# CPU.net
KiCad netlist of a schematic drawn in Altium Designer
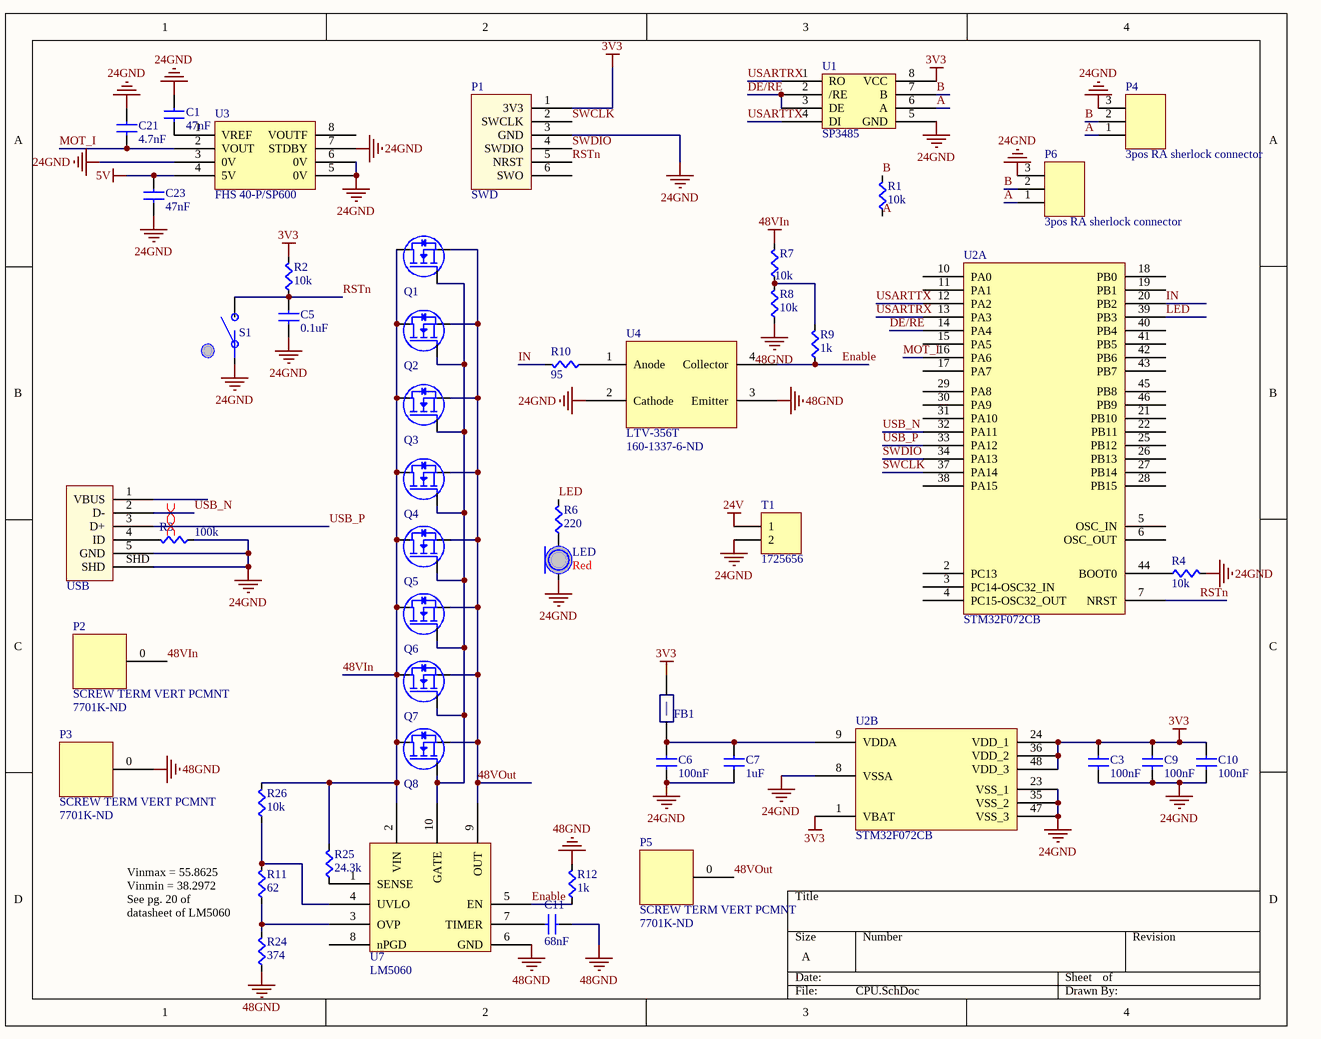
[diagram p0: CPU.SchDoc]

(export (version "E")
  (design (tool "Eeschema 10.0.6"))
  (components
    (comp (ref "C1")
      (value "47nF")
      (footprint "CAPC0603")
      (fields (field (name "Comment") "Cap"))
      (libsource (lib "SubjuGator8") (part "Cap"))
    )
    (comp (ref "C3")
      (value "100nF")
      (footprint "CAPC0603")
      (fields (field (name "Comment") "Cap"))
      (libsource (lib "SubjuGator8") (part "Cap"))
    )
    (comp (ref "C5")
      (value "0.1uF")
      (footprint "CAPC0603")
      (fields (field (name "Comment") "Cap"))
      (libsource (lib "SubjuGator8") (part "Cap"))
    )
    (comp (ref "C6")
      (value "100nF")
      (footprint "CAPC0603")
      (fields (field (name "Comment") "Cap"))
      (libsource (lib "SubjuGator8") (part "Cap"))
    )
    (comp (ref "C7")
      (value "1uF")
      (footprint "CAPC0603")
      (fields (field (name "Comment") "Cap"))
      (libsource (lib "SubjuGator8") (part "Cap"))
    )
    (comp (ref "C9")
      (value "100nF")
      (footprint "CAPC0603")
      (fields (field (name "Comment") "Cap"))
      (libsource (lib "SubjuGator8") (part "Cap"))
    )
    (comp (ref "C10")
      (value "100nF")
      (footprint "CAPC0603")
      (fields (field (name "Comment") "Cap"))
      (libsource (lib "SubjuGator8") (part "Cap"))
    )
    (comp (ref "C11")
      (value "68nF")
      (footprint "CAPC0603")
      (fields (field (name "Comment") "Cap"))
      (libsource (lib "SubjuGator8") (part "Cap"))
    )
    (comp (ref "C21")
      (value "4.7nF")
      (footprint "CAPC0603")
      (fields (field (name "Comment") "Cap"))
      (libsource (lib "SubjuGator8") (part "Cap"))
    )
    (comp (ref "C23")
      (value "47nF")
      (footprint "CAPC0603")
      (fields (field (name "Comment") "Cap"))
      (libsource (lib "SubjuGator8") (part "Cap"))
    )
    (comp (ref "FB1")
      (value "FBead")
      (footprint "RES0603")
      (description "Ferrite Bead")
      (libsource (lib "SubjuGator8") (part "FBead"))
    )
    (comp (ref "LED")
      (value "LED")
      (footprint "LED0603")
      (fields (field (name "COLOR") "Red"))
      (libsource (lib "SubjuGator8") (part "LED"))
    )
    (comp (ref "P1")
      (value "SWD")
      (footprint "SWD_STM32")
      (description "SWD connector matching the pinout on STM Discovery Boards")
      (libsource (lib "SubjuGator8") (part "SWD_STM32"))
    )
    (comp (ref "P2")
      (value "SCREW TERM VERT PCMNT")
      (footprint "SCREW TERM SINGLE VERT")
      (description "Keystone Electronics 7701")
      (fields (field (name "SUPPLIER PART NUMBER 1") "7701K-ND"))
      (libsource (lib "SubjuGator8") (part "SCREW TERM VERT PCMNT"))
    )
    (comp (ref "P3")
      (value "SCREW TERM VERT PCMNT")
      (footprint "SCREW TERM SINGLE VERT")
      (description "Keystone Electronics 7701")
      (fields (field (name "SUPPLIER PART NUMBER 1") "7701K-ND"))
      (libsource (lib "SubjuGator8") (part "SCREW TERM VERT PCMNT"))
    )
    (comp (ref "P4")
      (value "3pos RA sherlock connector")
      (footprint "MOLEX-HDR-1X3-SHERLOCK-RA")
      (description "Header, Molex, 2mm Pitch Sherlock Header, Single Row, Right Angle 3 Circuits, Length 3.3mm")
      (fields
        (field (name "MANUFACTURER PART NUMBER") "35363-0360")
        (field (name "MANUFACTURER") "Molex Connector Corporation")
      )
      (libsource (lib "SubjuGator8") (part "MOLEX-HDR-1x3-SHERLOCK_RA"))
    )
    (comp (ref "P5")
      (value "SCREW TERM VERT PCMNT")
      (footprint "SCREW TERM SINGLE VERT")
      (description "Keystone Electronics 7701")
      (fields (field (name "SUPPLIER PART NUMBER 1") "7701K-ND"))
      (libsource (lib "SubjuGator8") (part "SCREW TERM VERT PCMNT"))
    )
    (comp (ref "P6")
      (value "3pos RA sherlock connector")
      (footprint "MOLEX-HDR-1X3-SHERLOCK-RA")
      (description "Header, Molex, 2mm Pitch Sherlock Header, Single Row, Right Angle 3 Circuits, Length 3.3mm")
      (fields
        (field (name "MANUFACTURER PART NUMBER") "35363-0360")
        (field (name "MANUFACTURER") "Molex Connector Corporation")
      )
      (libsource (lib "SubjuGator8") (part "MOLEX-HDR-1x3-SHERLOCK_RA"))
    )
    (comp (ref "Q1")
      (value "CSD19502Q5B")
      (footprint "CSD19502Q5B")
      (description "NEXFET Power MOSFET")
      (libsource (lib "SubjuGator8") (part "CSD19502Q5B"))
    )
    (comp (ref "Q2")
      (value "CSD19502Q5B")
      (footprint "CSD19502Q5B")
      (description "NEXFET Power MOSFET")
      (libsource (lib "SubjuGator8") (part "CSD19502Q5B"))
    )
    (comp (ref "Q3")
      (value "CSD19502Q5B")
      (footprint "CSD19502Q5B")
      (description "NEXFET Power MOSFET")
      (libsource (lib "SubjuGator8") (part "CSD19502Q5B"))
    )
    (comp (ref "Q4")
      (value "CSD19502Q5B")
      (footprint "CSD19502Q5B")
      (description "NEXFET Power MOSFET")
      (libsource (lib "SubjuGator8") (part "CSD19502Q5B"))
    )
    (comp (ref "Q5")
      (value "CSD19502Q5B")
      (footprint "CSD19502Q5B")
      (description "NEXFET Power MOSFET")
      (libsource (lib "SubjuGator8") (part "CSD19502Q5B"))
    )
    (comp (ref "Q6")
      (value "CSD19502Q5B")
      (footprint "CSD19502Q5B")
      (description "NEXFET Power MOSFET")
      (libsource (lib "SubjuGator8") (part "CSD19502Q5B"))
    )
    (comp (ref "Q7")
      (value "CSD19502Q5B")
      (footprint "CSD19502Q5B")
      (description "NEXFET Power MOSFET")
      (libsource (lib "SubjuGator8") (part "CSD19502Q5B"))
    )
    (comp (ref "Q8")
      (value "CSD19502Q5B")
      (footprint "CSD19502Q5B")
      (description "NEXFET Power MOSFET")
      (libsource (lib "SubjuGator8") (part "CSD19502Q5B"))
    )
    (comp (ref "R1")
      (value "10k")
      (footprint "RES0603")
      (fields (field (name "Comment") "Res"))
      (libsource (lib "SubjuGator8") (part "Res"))
    )
    (comp (ref "R2")
      (value "10k")
      (footprint "RES0603")
      (fields (field (name "Comment") "Res"))
      (libsource (lib "SubjuGator8") (part "Res"))
    )
    (comp (ref "R3")
      (value "100k")
      (footprint "RES0603")
      (fields (field (name "Comment") "Res"))
      (libsource (lib "SubjuGator8") (part "Res"))
    )
    (comp (ref "R4")
      (value "10k")
      (footprint "RES0603")
      (fields (field (name "Comment") "Res"))
      (libsource (lib "SubjuGator8") (part "Res"))
    )
    (comp (ref "R6")
      (value "220")
      (footprint "RES0603")
      (fields (field (name "Comment") "Res"))
      (libsource (lib "SubjuGator8") (part "Res"))
    )
    (comp (ref "R7")
      (value "10k")
      (footprint "RES0603")
      (fields (field (name "Comment") "Res"))
      (libsource (lib "SubjuGator8") (part "Res"))
    )
    (comp (ref "R8")
      (value "10k")
      (footprint "RES0603")
      (fields (field (name "Comment") "Res"))
      (libsource (lib "SubjuGator8") (part "Res"))
    )
    (comp (ref "R9")
      (value "1k")
      (footprint "RES0603")
      (fields (field (name "Comment") "Res"))
      (libsource (lib "SubjuGator8") (part "Res"))
    )
    (comp (ref "R10")
      (value "95")
      (footprint "RES0603")
      (fields (field (name "Comment") "Res"))
      (libsource (lib "SubjuGator8") (part "Res"))
    )
    (comp (ref "R11")
      (value "62")
      (footprint "RES0603")
      (fields (field (name "Comment") "Res"))
      (libsource (lib "SubjuGator8") (part "Res"))
    )
    (comp (ref "R12")
      (value "1k")
      (footprint "RES0603")
      (fields (field (name "Comment") "Res"))
      (libsource (lib "SubjuGator8") (part "Res"))
    )
    (comp (ref "R24")
      (value "374")
      (footprint "RES0603")
      (fields (field (name "Comment") "Res"))
      (libsource (lib "SubjuGator8") (part "Res"))
    )
    (comp (ref "R25")
      (value "24.3k")
      (footprint "RES0603")
      (fields (field (name "Comment") "Res"))
      (libsource (lib "SubjuGator8") (part "Res"))
    )
    (comp (ref "R26")
      (value "10k")
      (footprint "RES0603")
      (fields (field (name "Comment") "Res"))
      (libsource (lib "SubjuGator8") (part "Res"))
    )
    (comp (ref "S1")
      (value "Button")
      (footprint "PTS645xxxxSMTR92")
      (description "SPST Button")
      (libsource (lib "SubjuGator8") (part "Button"))
    )
    (comp (ref "T1")
      (value "1725656")
      (footprint "1725656")
      (description "CONN TERM BLOCK 2.54MM 2POS")
      (libsource (lib "SubjuGator8") (part "1725656"))
    )
    (comp (ref "U1")
      (value "SP3485")
      (footprint "SP3485")
      (description "IC TXRX RS485 HALF DUPLEX 8NSOIC")
      (libsource (lib "SubjuGator8") (part "SP3485"))
    )
    (comp (ref "U2")
      (value "STM32F072CB")
      (footprint "STM32F072CB")
      (description "MCU 32BIT 128KB FLASH 48LQFP")
      (libsource (lib "SubjuGator8") (part "STM32F072CB"))
    )
    (comp (ref "U3")
      (value "FHS 40-P/SP600")
      (footprint "FHS 40-P/SP600")
      (libsource (lib "SubjuGator8") (part "FHS 40-P/SP600"))
    )
    (comp (ref "U4")
      (value "LTV-356T")
      (footprint "LTV-356T")
      (description "OPTOISOLATOR 3.75KV TRANS 4-SOP")
      (fields (field (name "SUPPLIER PART NUMBER 1") "160-1337-6-ND"))
      (libsource (lib "SubjuGator8") (part "LTV-356T"))
    )
    (comp (ref "U7")
      (value "LM5060")
      (footprint "LM5060")
      (description "Hotswap Controller")
      (libsource (lib "SubjuGator8") (part "LM5060"))
    )
    (comp (ref "USB")
      (value "USB Micro")
      (footprint "10118192-0001LF")
      (description "USB Mini B Metal Shield SMT")
      (libsource (lib "SubjuGator8") (part "USB Micro"))
    )
  )
  (nets
    (net (code "1") (name "/48VOut") (class "Default")
      (node (ref "P5") (pin "0") (pinfunction "1_0") (pintype "passive"))
      (node (ref "Q1") (pin "S") (pinfunction "S_S") (pintype "passive"))
      (node (ref "Q2") (pin "S") (pinfunction "S_S") (pintype "passive"))
      (node (ref "Q3") (pin "S") (pinfunction "S_S") (pintype "passive"))
      (node (ref "Q4") (pin "S") (pinfunction "S_S") (pintype "passive"))
      (node (ref "Q5") (pin "S") (pinfunction "S_S") (pintype "passive"))
      (node (ref "Q6") (pin "S") (pinfunction "S_S") (pintype "passive"))
      (node (ref "Q7") (pin "S") (pinfunction "S_S") (pintype "passive"))
      (node (ref "Q8") (pin "S") (pinfunction "S_S") (pintype "passive"))
      (node (ref "U7") (pin "9") (pinfunction "OUT_9") (pintype "passive"))
    )
    (net (code "2") (name "/A") (class "Default")
      (node (ref "P4") (pin "1") (pinfunction "1_1") (pintype "passive"))
      (node (ref "P6") (pin "1") (pinfunction "1_1") (pintype "passive"))
      (node (ref "R1") (pin "2") (pinfunction "B_2") (pintype "passive"))
      (node (ref "U1") (pin "6") (pinfunction "A_6") (pintype "passive"))
    )
    (net (code "3") (name "/B") (class "Default")
      (node (ref "P4") (pin "2") (pinfunction "2_2") (pintype "passive"))
      (node (ref "P6") (pin "2") (pinfunction "2_2") (pintype "passive"))
      (node (ref "R1") (pin "1") (pinfunction "A_1") (pintype "passive"))
      (node (ref "U1") (pin "7") (pinfunction "B_7") (pintype "passive"))
    )
    (net (code "4") (name "/DE{slash}RE") (class "Default")
      (node (ref "U1") (pin "2") (pinfunction "/RE_2") (pintype "passive"))
      (node (ref "U1") (pin "3") (pinfunction "DE_3") (pintype "passive"))
      (node (ref "U2") (pin "14") (pinfunction "PA4_14") (pintype "passive"))
    )
    (net (code "5") (name "/Enable") (class "Default")
      (node (ref "R12") (pin "2") (pinfunction "B_2") (pintype "passive"))
      (node (ref "R9") (pin "2") (pinfunction "B_2") (pintype "passive"))
      (node (ref "U4") (pin "4") (pinfunction "Collector_4") (pintype "passive"))
      (node (ref "U7") (pin "5") (pinfunction "EN_5") (pintype "passive"))
    )
    (net (code "6") (name "/IN") (class "Default")
      (node (ref "R10") (pin "1") (pinfunction "A_1") (pintype "passive"))
      (node (ref "U2") (pin "20") (pinfunction "PB2_20") (pintype "passive"))
    )
    (net (code "7") (name "/LED") (class "Default")
      (node (ref "R6") (pin "1") (pinfunction "A_1") (pintype "passive"))
      (node (ref "U2") (pin "39") (pinfunction "PB3_39") (pintype "passive"))
    )
    (net (code "8") (name "/MOT_I") (class "Default")
      (node (ref "C21") (pin "1") (pinfunction "A_1") (pintype "passive"))
      (node (ref "U2") (pin "16") (pinfunction "PA6_16") (pintype "passive"))
      (node (ref "U3") (pin "2") (pinfunction "VOUT_2") (pintype "passive"))
    )
    (net (code "9") (name "/RSTn") (class "Default")
      (node (ref "C5") (pin "1") (pinfunction "A_1") (pintype "passive"))
      (node (ref "P1") (pin "5") (pinfunction "NRST_5") (pintype "passive"))
      (node (ref "R2") (pin "2") (pinfunction "B_2") (pintype "passive"))
      (node (ref "S1") (pin "B") (pinfunction "B_B") (pintype "passive"))
      (node (ref "U2") (pin "7") (pinfunction "NRST_7") (pintype "passive"))
    )
    (net (code "10") (name "/SWCLK") (class "Default")
      (node (ref "P1") (pin "2") (pinfunction "SWCLK_2") (pintype "passive"))
      (node (ref "U2") (pin "37") (pinfunction "PA14_37") (pintype "passive"))
    )
    (net (code "11") (name "/SWDIO") (class "Default")
      (node (ref "P1") (pin "4") (pinfunction "SWDIO_4") (pintype "passive"))
      (node (ref "U2") (pin "34") (pinfunction "PA13_34") (pintype "passive"))
    )
    (net (code "12") (name "/USARTRX") (class "Default")
      (node (ref "U1") (pin "1") (pinfunction "RO_1") (pintype "passive"))
      (node (ref "U2") (pin "13") (pinfunction "PA3_13") (pintype "passive"))
    )
    (net (code "13") (name "/USARTTX") (class "Default")
      (node (ref "U1") (pin "4") (pinfunction "DI_4") (pintype "passive"))
      (node (ref "U2") (pin "12") (pinfunction "PA2_12") (pintype "passive"))
    )
    (net (code "14") (name "/USB_N") (class "Default")
      (node (ref "U2") (pin "32") (pinfunction "PA11_32") (pintype "passive"))
      (node (ref "USB") (pin "2") (pinfunction "D-_2") (pintype "passive"))
    )
    (net (code "15") (name "/USB_P") (class "Default")
      (node (ref "U2") (pin "33") (pinfunction "PA12_33") (pintype "passive"))
      (node (ref "USB") (pin "3") (pinfunction "D+_3") (pintype "passive"))
    )
    (net (code "16") (name "3V3") (class "Default")
      (node (ref "C10") (pin "1") (pinfunction "A_1") (pintype "passive"))
      (node (ref "C3") (pin "1") (pinfunction "A_1") (pintype "passive"))
      (node (ref "C9") (pin "1") (pinfunction "A_1") (pintype "passive"))
      (node (ref "FB1") (pin "2") (pinfunction "B_2") (pintype "passive"))
      (node (ref "P1") (pin "1") (pinfunction "3V3_1") (pintype "passive"))
      (node (ref "R2") (pin "1") (pinfunction "A_1") (pintype "passive"))
      (node (ref "U1") (pin "8") (pinfunction "VCC_8") (pintype "passive"))
      (node (ref "U2") (pin "1") (pinfunction "VBAT_1") (pintype "passive"))
      (node (ref "U2") (pin "24") (pinfunction "VDD_1_24") (pintype "passive"))
      (node (ref "U2") (pin "36") (pinfunction "VDD_2_36") (pintype "passive"))
      (node (ref "U2") (pin "48") (pinfunction "VDD_3_48") (pintype "passive"))
    )
    (net (code "17") (name "5V") (class "Default")
      (node (ref "C23") (pin "1") (pinfunction "A_1") (pintype "passive"))
      (node (ref "U3") (pin "4") (pinfunction "5V_4") (pintype "passive"))
    )
    (net (code "18") (name "24GND") (class "Default")
      (node (ref "C1") (pin "1") (pinfunction "A_1") (pintype "passive"))
      (node (ref "C10") (pin "2") (pinfunction "B_2") (pintype "passive"))
      (node (ref "C21") (pin "2") (pinfunction "B_2") (pintype "passive"))
      (node (ref "C23") (pin "2") (pinfunction "B_2") (pintype "passive"))
      (node (ref "C3") (pin "2") (pinfunction "B_2") (pintype "passive"))
      (node (ref "C5") (pin "2") (pinfunction "B_2") (pintype "passive"))
      (node (ref "C6") (pin "2") (pinfunction "B_2") (pintype "passive"))
      (node (ref "C7") (pin "2") (pinfunction "B_2") (pintype "passive"))
      (node (ref "C9") (pin "2") (pinfunction "B_2") (pintype "passive"))
      (node (ref "LED") (pin "C") (pinfunction "C_C") (pintype "passive"))
      (node (ref "P1") (pin "3") (pinfunction "GND_3") (pintype "passive"))
      (node (ref "P4") (pin "3") (pinfunction "3_3") (pintype "passive"))
      (node (ref "P6") (pin "3") (pinfunction "3_3") (pintype "passive"))
      (node (ref "R3") (pin "2") (pinfunction "B_2") (pintype "passive"))
      (node (ref "R4") (pin "1") (pinfunction "A_1") (pintype "passive"))
      (node (ref "S1") (pin "A") (pinfunction "A_A") (pintype "passive"))
      (node (ref "T1") (pin "2") (pinfunction "2_2") (pintype "passive"))
      (node (ref "U1") (pin "5") (pinfunction "GND_5") (pintype "passive"))
      (node (ref "U2") (pin "23") (pinfunction "VSS_1_23") (pintype "passive"))
      (node (ref "U2") (pin "35") (pinfunction "VSS_2_35") (pintype "passive"))
      (node (ref "U2") (pin "47") (pinfunction "VSS_3_47") (pintype "passive"))
      (node (ref "U2") (pin "8") (pinfunction "VSSA_8") (pintype "passive"))
      (node (ref "U3") (pin "3") (pinfunction "0V_3") (pintype "passive"))
      (node (ref "U3") (pin "5") (pinfunction "0V_5") (pintype "passive"))
      (node (ref "U3") (pin "6") (pinfunction "0V_6") (pintype "passive"))
      (node (ref "U3") (pin "7") (pinfunction "STDBY_7") (pintype "passive"))
      (node (ref "U4") (pin "2") (pinfunction "Cathode_2") (pintype "passive"))
      (node (ref "USB") (pin "5") (pinfunction "GND_5") (pintype "passive"))
      (node (ref "USB") (pin "SHD") (pinfunction "SHD_SHD") (pintype "passive"))
    )
    (net (code "19") (name "24V") (class "Default")
      (node (ref "T1") (pin "1") (pinfunction "1_1") (pintype "passive"))
    )
    (net (code "20") (name "48GND") (class "Default")
      (node (ref "C11") (pin "2") (pinfunction "B_2") (pintype "passive"))
      (node (ref "P3") (pin "0") (pinfunction "1_0") (pintype "passive"))
      (node (ref "R12") (pin "1") (pinfunction "A_1") (pintype "passive"))
      (node (ref "R24") (pin "2") (pinfunction "B_2") (pintype "passive"))
      (node (ref "R8") (pin "2") (pinfunction "B_2") (pintype "passive"))
      (node (ref "U4") (pin "3") (pinfunction "Emitter_3") (pintype "passive"))
      (node (ref "U7") (pin "6") (pinfunction "GND_6") (pintype "passive"))
    )
    (net (code "21") (name "48VIn") (class "Default")
      (node (ref "P2") (pin "0") (pinfunction "1_0") (pintype "passive"))
      (node (ref "Q1") (pin "D") (pinfunction "D_D") (pintype "passive"))
      (node (ref "Q2") (pin "D") (pinfunction "D_D") (pintype "passive"))
      (node (ref "Q3") (pin "D") (pinfunction "D_D") (pintype "passive"))
      (node (ref "Q4") (pin "D") (pinfunction "D_D") (pintype "passive"))
      (node (ref "Q5") (pin "D") (pinfunction "D_D") (pintype "passive"))
      (node (ref "Q6") (pin "D") (pinfunction "D_D") (pintype "passive"))
      (node (ref "Q7") (pin "D") (pinfunction "D_D") (pintype "passive"))
      (node (ref "Q8") (pin "D") (pinfunction "D_D") (pintype "passive"))
      (node (ref "R25") (pin "1") (pinfunction "A_1") (pintype "passive"))
      (node (ref "R26") (pin "1") (pinfunction "A_1") (pintype "passive"))
      (node (ref "R7") (pin "1") (pinfunction "A_1") (pintype "passive"))
      (node (ref "U7") (pin "2") (pinfunction "VIN_2") (pintype "passive"))
    )
    (net (code "22") (name "Net-(C1-B)") (class "Default")
      (node (ref "C1") (pin "2") (pinfunction "B_2") (pintype "passive"))
      (node (ref "U3") (pin "1") (pinfunction "VREF_1") (pintype "passive"))
    )
    (net (code "23") (name "Net-(C6-A)") (class "Default")
      (node (ref "C6") (pin "1") (pinfunction "A_1") (pintype "passive"))
      (node (ref "C7") (pin "1") (pinfunction "A_1") (pintype "passive"))
      (node (ref "FB1") (pin "1") (pinfunction "A_1") (pintype "passive"))
      (node (ref "U2") (pin "9") (pinfunction "VDDA_9") (pintype "passive"))
    )
    (net (code "24") (name "Net-(C11-A)") (class "Default")
      (node (ref "C11") (pin "1") (pinfunction "A_1") (pintype "passive"))
      (node (ref "U7") (pin "7") (pinfunction "TIMER_7") (pintype "passive"))
    )
    (net (code "25") (name "Net-(R3-A)") (class "Default")
      (node (ref "R3") (pin "1") (pinfunction "A_1") (pintype "passive"))
      (node (ref "USB") (pin "4") (pinfunction "ID_4") (pintype "passive"))
    )
    (net (code "26") (name "Net-(R4-B)") (class "Default")
      (node (ref "R4") (pin "2") (pinfunction "B_2") (pintype "passive"))
      (node (ref "U2") (pin "44") (pinfunction "BOOT0_44") (pintype "passive"))
    )
    (net (code "27") (name "Net-(R6-B)") (class "Default")
      (node (ref "LED") (pin "A") (pinfunction "A_A") (pintype "passive"))
      (node (ref "R6") (pin "2") (pinfunction "B_2") (pintype "passive"))
    )
    (net (code "28") (name "Net-(R7-B)") (class "Default")
      (node (ref "R7") (pin "2") (pinfunction "B_2") (pintype "passive"))
      (node (ref "R8") (pin "1") (pinfunction "A_1") (pintype "passive"))
      (node (ref "R9") (pin "1") (pinfunction "A_1") (pintype "passive"))
    )
    (net (code "29") (name "Net-(R10-B)") (class "Default")
      (node (ref "R10") (pin "2") (pinfunction "B_2") (pintype "passive"))
      (node (ref "U4") (pin "1") (pinfunction "Anode_1") (pintype "passive"))
    )
    (net (code "30") (name "Net-(R11-A)") (class "Default")
      (node (ref "R11") (pin "1") (pinfunction "A_1") (pintype "passive"))
      (node (ref "R26") (pin "2") (pinfunction "B_2") (pintype "passive"))
      (node (ref "U7") (pin "4") (pinfunction "UVLO_4") (pintype "passive"))
    )
    (net (code "31") (name "Net-(R11-B)") (class "Default")
      (node (ref "R11") (pin "2") (pinfunction "B_2") (pintype "passive"))
      (node (ref "R24") (pin "1") (pinfunction "A_1") (pintype "passive"))
      (node (ref "U7") (pin "3") (pinfunction "OVP_3") (pintype "passive"))
    )
    (net (code "32") (name "Net-(R25-B)") (class "Default")
      (node (ref "R25") (pin "2") (pinfunction "B_2") (pintype "passive"))
      (node (ref "U7") (pin "1") (pinfunction "SENSE_1") (pintype "passive"))
    )
    (net (code "33") (name "Net-(U7-GATE)") (class "Default")
      (node (ref "Q1") (pin "G") (pinfunction "G_G") (pintype "passive"))
      (node (ref "Q2") (pin "G") (pinfunction "G_G") (pintype "passive"))
      (node (ref "Q3") (pin "G") (pinfunction "G_G") (pintype "passive"))
      (node (ref "Q4") (pin "G") (pinfunction "G_G") (pintype "passive"))
      (node (ref "Q5") (pin "G") (pinfunction "G_G") (pintype "passive"))
      (node (ref "Q6") (pin "G") (pinfunction "G_G") (pintype "passive"))
      (node (ref "Q7") (pin "G") (pinfunction "G_G") (pintype "passive"))
      (node (ref "Q8") (pin "G") (pinfunction "G_G") (pintype "passive"))
      (node (ref "U7") (pin "10") (pinfunction "GATE_10") (pintype "passive"))
    )
    (net (code "34") (name "unconnected-(P1-SWO-Pad6)") (class "Default")
      (node (ref "P1") (pin "6") (pinfunction "SWO_6") (pintype "passive"))
    )
    (net (code "35") (name "unconnected-(U2A-OSC_IN-Pad5)") (class "Default")
      (node (ref "U2") (pin "5") (pinfunction "OSC_IN_5") (pintype "passive"))
    )
    (net (code "36") (name "unconnected-(U2A-OSC_OUT-Pad6)") (class "Default")
      (node (ref "U2") (pin "6") (pinfunction "OSC_OUT_6") (pintype "passive"))
    )
    (net (code "37") (name "unconnected-(U2A-PA0-Pad10)") (class "Default")
      (node (ref "U2") (pin "10") (pinfunction "PA0_10") (pintype "passive"))
    )
    (net (code "38") (name "unconnected-(U2A-PA1-Pad11)") (class "Default")
      (node (ref "U2") (pin "11") (pinfunction "PA1_11") (pintype "passive"))
    )
    (net (code "39") (name "unconnected-(U2A-PA5-Pad15)") (class "Default")
      (node (ref "U2") (pin "15") (pinfunction "PA5_15") (pintype "passive"))
    )
    (net (code "40") (name "unconnected-(U2A-PA7-Pad17)") (class "Default")
      (node (ref "U2") (pin "17") (pinfunction "PA7_17") (pintype "passive"))
    )
    (net (code "41") (name "unconnected-(U2A-PA8-Pad29)") (class "Default")
      (node (ref "U2") (pin "29") (pinfunction "PA8_29") (pintype "passive"))
    )
    (net (code "42") (name "unconnected-(U2A-PA9-Pad30)") (class "Default")
      (node (ref "U2") (pin "30") (pinfunction "PA9_30") (pintype "passive"))
    )
    (net (code "43") (name "unconnected-(U2A-PA10-Pad31)") (class "Default")
      (node (ref "U2") (pin "31") (pinfunction "PA10_31") (pintype "passive"))
    )
    (net (code "44") (name "unconnected-(U2A-PA15-Pad38)") (class "Default")
      (node (ref "U2") (pin "38") (pinfunction "PA15_38") (pintype "passive"))
    )
    (net (code "45") (name "unconnected-(U2A-PB0-Pad18)") (class "Default")
      (node (ref "U2") (pin "18") (pinfunction "PB0_18") (pintype "passive"))
    )
    (net (code "46") (name "unconnected-(U2A-PB1-Pad19)") (class "Default")
      (node (ref "U2") (pin "19") (pinfunction "PB1_19") (pintype "passive"))
    )
    (net (code "47") (name "unconnected-(U2A-PB4-Pad40)") (class "Default")
      (node (ref "U2") (pin "40") (pinfunction "PB4_40") (pintype "passive"))
    )
    (net (code "48") (name "unconnected-(U2A-PB5-Pad41)") (class "Default")
      (node (ref "U2") (pin "41") (pinfunction "PB5_41") (pintype "passive"))
    )
    (net (code "49") (name "unconnected-(U2A-PB6-Pad42)") (class "Default")
      (node (ref "U2") (pin "42") (pinfunction "PB6_42") (pintype "passive"))
    )
    (net (code "50") (name "unconnected-(U2A-PB7-Pad43)") (class "Default")
      (node (ref "U2") (pin "43") (pinfunction "PB7_43") (pintype "passive"))
    )
    (net (code "51") (name "unconnected-(U2A-PB8-Pad45)") (class "Default")
      (node (ref "U2") (pin "45") (pinfunction "PB8_45") (pintype "passive"))
    )
    (net (code "52") (name "unconnected-(U2A-PB9-Pad46)") (class "Default")
      (node (ref "U2") (pin "46") (pinfunction "PB9_46") (pintype "passive"))
    )
    (net (code "53") (name "unconnected-(U2A-PB10-Pad21)") (class "Default")
      (node (ref "U2") (pin "21") (pinfunction "PB10_21") (pintype "passive"))
    )
    (net (code "54") (name "unconnected-(U2A-PB11-Pad22)") (class "Default")
      (node (ref "U2") (pin "22") (pinfunction "PB11_22") (pintype "passive"))
    )
    (net (code "55") (name "unconnected-(U2A-PB12-Pad25)") (class "Default")
      (node (ref "U2") (pin "25") (pinfunction "PB12_25") (pintype "passive"))
    )
    (net (code "56") (name "unconnected-(U2A-PB13-Pad26)") (class "Default")
      (node (ref "U2") (pin "26") (pinfunction "PB13_26") (pintype "passive"))
    )
    (net (code "57") (name "unconnected-(U2A-PB14-Pad27)") (class "Default")
      (node (ref "U2") (pin "27") (pinfunction "PB14_27") (pintype "passive"))
    )
    (net (code "58") (name "unconnected-(U2A-PB15-Pad28)") (class "Default")
      (node (ref "U2") (pin "28") (pinfunction "PB15_28") (pintype "passive"))
    )
    (net (code "59") (name "unconnected-(U2A-PC13-Pad2)") (class "Default")
      (node (ref "U2") (pin "2") (pinfunction "PC13_2") (pintype "passive"))
    )
    (net (code "60") (name "unconnected-(U2A-PC14-OSC32_IN-Pad3)") (class "Default")
      (node (ref "U2") (pin "3") (pinfunction "PC14-OSC32_IN_3") (pintype "passive"))
    )
    (net (code "61") (name "unconnected-(U2A-PC15-OSC32_OUT-Pad4)") (class "Default")
      (node (ref "U2") (pin "4") (pinfunction "PC15-OSC32_OUT_4") (pintype "passive"))
    )
    (net (code "62") (name "unconnected-(U3-VOUTF-Pad8)") (class "Default")
      (node (ref "U3") (pin "8") (pinfunction "VOUTF_8") (pintype "passive"))
    )
    (net (code "63") (name "unconnected-(U7-nPGD-Pad8)") (class "Default")
      (node (ref "U7") (pin "8") (pinfunction "nPGD_8") (pintype "passive"))
    )
    (net (code "64") (name "unconnected-(USB-VBUS-Pad1)") (class "Default")
      (node (ref "USB") (pin "1") (pinfunction "VBUS_1") (pintype "passive"))
    )
  )
)
